# TS-ARM3_0_9.net
KiCad netlist of a schematic drawn in EAGLE
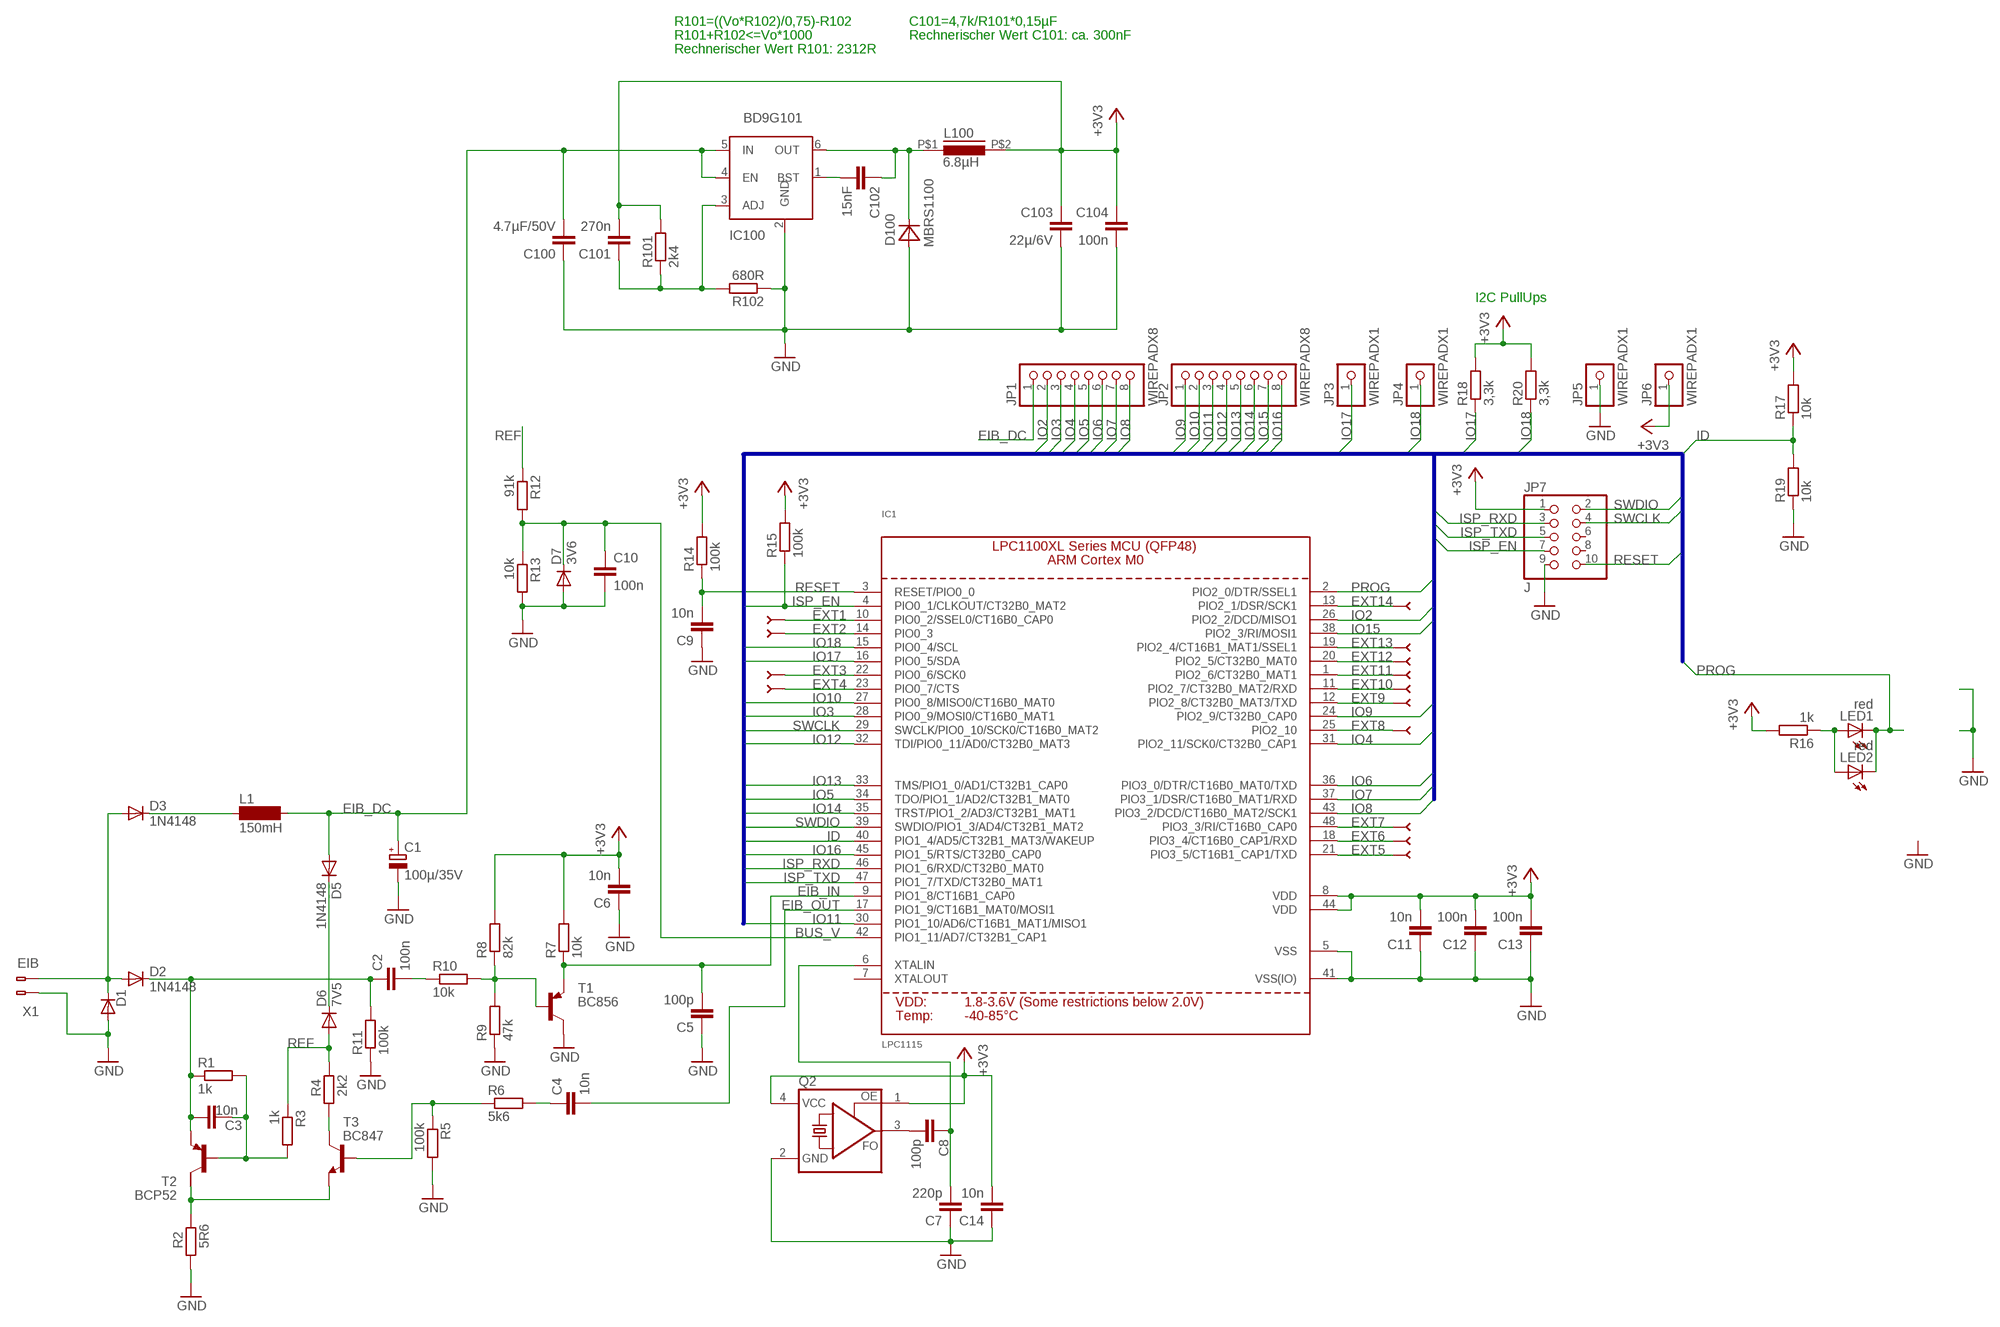
[diagram p0: schematic, sheet 1]

(export (version "E")
  (design (tool "Eeschema 10.0.6"))
  (components
    (comp (ref "C1")
      (value "100µ/35V")
      (footprint "eagle-import:SANYO-OSCON_SMD_C6")
      (libsource (lib "eagle-import") (part "CPOL-EUSANYO_SMD_C6"))
    )
    (comp (ref "C2")
      (value "100n")
      (footprint "eagle-import:C1206")
      (libsource (lib "eagle-import") (part "C-EUC1206"))
    )
    (comp (ref "C3")
      (value "10n")
      (footprint "eagle-import:C1206")
      (libsource (lib "eagle-import") (part "C-EUC1206"))
    )
    (comp (ref "C4")
      (value "10n")
      (footprint "eagle-import:C1206")
      (libsource (lib "eagle-import") (part "C-EUC1206"))
    )
    (comp (ref "C5")
      (value "100p")
      (footprint "eagle-import:C1206")
      (libsource (lib "eagle-import") (part "C-EUC1206"))
    )
    (comp (ref "C6")
      (value "10n")
      (footprint "eagle-import:C1206")
      (libsource (lib "eagle-import") (part "C-EUC1206"))
    )
    (comp (ref "C7")
      (value "220p")
      (footprint "eagle-import:C1206")
      (libsource (lib "eagle-import") (part "C-EUC1206"))
    )
    (comp (ref "C8")
      (value "100p")
      (footprint "eagle-import:C1206")
      (libsource (lib "eagle-import") (part "C-EUC1206"))
    )
    (comp (ref "C9")
      (value "10n")
      (footprint "eagle-import:C1206")
      (libsource (lib "eagle-import") (part "C-EUC1206"))
    )
    (comp (ref "C10")
      (value "100n")
      (footprint "eagle-import:C1206")
      (libsource (lib "eagle-import") (part "C-EUC1206"))
    )
    (comp (ref "C11")
      (value "10n")
      (footprint "eagle-import:C1206")
      (libsource (lib "eagle-import") (part "C-EUC1206"))
    )
    (comp (ref "C12")
      (value "100n")
      (footprint "eagle-import:C1206")
      (libsource (lib "eagle-import") (part "C-EUC1206"))
    )
    (comp (ref "C13")
      (value "100n")
      (footprint "eagle-import:C1206")
      (libsource (lib "eagle-import") (part "C-EUC1206"))
    )
    (comp (ref "C14")
      (value "10n")
      (footprint "eagle-import:C1206")
      (libsource (lib "eagle-import") (part "C-EUC1206"))
    )
    (comp (ref "C100")
      (value "4.7µF/50V")
      (footprint "eagle-import:C1206")
      (libsource (lib "eagle-import") (part "C-EUC1206"))
    )
    (comp (ref "C101")
      (value "270n")
      (footprint "eagle-import:C1206")
      (libsource (lib "eagle-import") (part "C-EUC1206"))
    )
    (comp (ref "C102")
      (value "15nF")
      (footprint "eagle-import:C1206")
      (libsource (lib "eagle-import") (part "C-EUC1206"))
    )
    (comp (ref "C103")
      (value "22µ/6V")
      (footprint "eagle-import:C1206")
      (libsource (lib "eagle-import") (part "C-EUC1206"))
    )
    (comp (ref "C104")
      (value "100n")
      (footprint "eagle-import:C1206")
      (libsource (lib "eagle-import") (part "C-EUC1206"))
    )
    (comp (ref "D1")
      (value "SMAJ40C")
      (footprint "eagle-import:SMB")
      (libsource (lib "eagle-import") (part "D-SMB"))
    )
    (comp (ref "D2")
      (value "1N4148")
      (footprint "eagle-import:MINIMELF")
      (libsource (lib "eagle-import") (part "DIODE-MINIMELF"))
    )
    (comp (ref "D3")
      (value "1N4148")
      (footprint "eagle-import:MINIMELF")
      (libsource (lib "eagle-import") (part "DIODE-MINIMELF"))
    )
    (comp (ref "D5")
      (value "1N4148")
      (footprint "eagle-import:MINIMELF")
      (libsource (lib "eagle-import") (part "DIODE-MINIMELF"))
    )
    (comp (ref "D6")
      (value "7V5")
      (footprint "eagle-import:MINIMELF")
      (libsource (lib "eagle-import") (part "DIODE-MINIMELF"))
    )
    (comp (ref "D7")
      (value "3V6")
      (footprint "eagle-import:MINIMELF")
      (libsource (lib "eagle-import") (part "DIODE-MINIMELF"))
    )
    (comp (ref "D100")
      (value "MBRS1100")
      (footprint "eagle-import:SMA")
      (libsource (lib "eagle-import") (part "MBRA340T3"))
    )
    (comp (ref "IC1")
      (value "LPC1115")
      (footprint "eagle-import:LQFP48")
      (libsource (lib "eagle-import") (part "LPC1113/4/5_QFP48_XLSERIES"))
    )
    (comp (ref "IC100")
      (value "BD9G101")
      (footprint "eagle-import:SOT23-6")
      (libsource (lib "eagle-import") (part "BD9G101GBD9G101G-SOT23-6"))
    )
    (comp (ref "JP1")
      (value "WIREPADX8")
      (footprint "eagle-import:SMD1,27X2,54X8")
      (libsource (lib "eagle-import") (part "WIREPADX8"))
    )
    (comp (ref "JP2")
      (value "WIREPADX8")
      (footprint "eagle-import:SMD1,27X2,54X8")
      (libsource (lib "eagle-import") (part "WIREPADX8"))
    )
    (comp (ref "JP3")
      (value "WIREPADX1")
      (footprint "eagle-import:SMD1,27X2,54")
      (libsource (lib "eagle-import") (part "WIREPADX1"))
    )
    (comp (ref "JP4")
      (value "WIREPADX1")
      (footprint "eagle-import:SMD1,27X2,54")
      (libsource (lib "eagle-import") (part "WIREPADX1"))
    )
    (comp (ref "JP5")
      (value "WIREPADX1")
      (footprint "eagle-import:SMD1,27X2,54")
      (libsource (lib "eagle-import") (part "WIREPADX1"))
    )
    (comp (ref "JP6")
      (value "WIREPADX1")
      (footprint "eagle-import:SMD1,27X2,54")
      (libsource (lib "eagle-import") (part "WIREPADX1"))
    )
    (comp (ref "JP7")
      (value "J")
      (footprint "eagle-import:2X05M")
      (libsource (lib "eagle-import") (part "PINHD-2X05_2.00"))
    )
    (comp (ref "L1")
      (value "150mH")
      (footprint "eagle-import:SD12_1000")
      (libsource (lib "eagle-import") (part "SD12-1000"))
    )
    (comp (ref "L100")
      (value "6.8µH")
      (footprint "eagle-import:PIS2812")
      (libsource (lib "eagle-import") (part "IND_FASTRON_1616FPS"))
    )
    (comp (ref "LED1")
      (value "red")
      (footprint "eagle-import:CHIPLED_1206")
      (libsource (lib "eagle-import") (part "LEDCHIPLED_1206"))
    )
    (comp (ref "LED2")
      (value "red")
      (footprint "eagle-import:LED3MM")
      (libsource (lib "eagle-import") (part "LED3MM"))
    )
    (comp (ref "P1")
      (value "PAD")
      (footprint "eagle-import:PAD")
      (libsource (lib "eagle-import") (part "PAD"))
    )
    (comp (ref "P2")
      (value "PAD")
      (footprint "eagle-import:PAD")
      (libsource (lib "eagle-import") (part "PAD"))
    )
    (comp (ref "P3")
      (value "PAD")
      (footprint "eagle-import:PAD")
      (libsource (lib "eagle-import") (part "PAD"))
    )
    (comp (ref "P4")
      (value "PAD")
      (footprint "eagle-import:PAD")
      (libsource (lib "eagle-import") (part "PAD"))
    )
    (comp (ref "P5")
      (value "PAD")
      (footprint "eagle-import:PAD")
      (libsource (lib "eagle-import") (part "PAD"))
    )
    (comp (ref "P6")
      (value "PAD")
      (footprint "eagle-import:PAD")
      (libsource (lib "eagle-import") (part "PAD"))
    )
    (comp (ref "P7")
      (value "PAD")
      (footprint "eagle-import:PAD")
      (libsource (lib "eagle-import") (part "PAD"))
    )
    (comp (ref "P8")
      (value "PAD")
      (footprint "eagle-import:PAD")
      (libsource (lib "eagle-import") (part "PAD"))
    )
    (comp (ref "P9")
      (value "PAD")
      (footprint "eagle-import:PAD")
      (libsource (lib "eagle-import") (part "PAD"))
    )
    (comp (ref "P10")
      (value "PAD")
      (footprint "eagle-import:PAD")
      (libsource (lib "eagle-import") (part "PAD"))
    )
    (comp (ref "P11")
      (value "PAD")
      (footprint "eagle-import:PAD")
      (libsource (lib "eagle-import") (part "PAD"))
    )
    (comp (ref "P12")
      (value "PAD")
      (footprint "eagle-import:PAD")
      (libsource (lib "eagle-import") (part "PAD"))
    )
    (comp (ref "P13")
      (value "PAD")
      (footprint "eagle-import:PAD")
      (libsource (lib "eagle-import") (part "PAD"))
    )
    (comp (ref "P14")
      (value "PAD")
      (footprint "eagle-import:PAD")
      (libsource (lib "eagle-import") (part "PAD"))
    )
    (comp (ref "Q2")
      (value "ASFL")
      (footprint "eagle-import:ASF")
      (libsource (lib "eagle-import") (part "ASFL"))
    )
    (comp (ref "R1")
      (value "1k")
      (footprint "eagle-import:R1206")
      (libsource (lib "eagle-import") (part "R-EU_R1206"))
    )
    (comp (ref "R2")
      (value "5R6")
      (footprint "eagle-import:R1206")
      (libsource (lib "eagle-import") (part "R-EU_R1206"))
    )
    (comp (ref "R3")
      (value "1k")
      (footprint "eagle-import:R1206")
      (libsource (lib "eagle-import") (part "R-EU_R1206"))
    )
    (comp (ref "R4")
      (value "2k2")
      (footprint "eagle-import:R1206")
      (libsource (lib "eagle-import") (part "R-EU_R1206"))
    )
    (comp (ref "R5")
      (value "100k")
      (footprint "eagle-import:R1206")
      (libsource (lib "eagle-import") (part "R-EU_R1206"))
    )
    (comp (ref "R6")
      (value "5k6")
      (footprint "eagle-import:R1206")
      (libsource (lib "eagle-import") (part "R-EU_R1206"))
    )
    (comp (ref "R7")
      (value "10k")
      (footprint "eagle-import:R1206")
      (libsource (lib "eagle-import") (part "R-EU_R1206"))
    )
    (comp (ref "R8")
      (value "82k")
      (footprint "eagle-import:R1206")
      (libsource (lib "eagle-import") (part "R-EU_R1206"))
    )
    (comp (ref "R9")
      (value "47k")
      (footprint "eagle-import:R1206")
      (libsource (lib "eagle-import") (part "R-EU_R1206"))
    )
    (comp (ref "R10")
      (value "10k")
      (footprint "eagle-import:R1206")
      (libsource (lib "eagle-import") (part "R-EU_R1206"))
    )
    (comp (ref "R11")
      (value "100k")
      (footprint "eagle-import:R1206")
      (libsource (lib "eagle-import") (part "R-EU_R1206"))
    )
    (comp (ref "R12")
      (value "91k")
      (footprint "eagle-import:R1206")
      (libsource (lib "eagle-import") (part "R-EU_R1206"))
    )
    (comp (ref "R13")
      (value "10k")
      (footprint "eagle-import:R1206")
      (libsource (lib "eagle-import") (part "R-EU_R1206"))
    )
    (comp (ref "R14")
      (value "100k")
      (footprint "eagle-import:R1206")
      (libsource (lib "eagle-import") (part "R-EU_R1206"))
    )
    (comp (ref "R15")
      (value "100k")
      (footprint "eagle-import:R1206")
      (libsource (lib "eagle-import") (part "R-EU_R1206"))
    )
    (comp (ref "R16")
      (value "1k")
      (footprint "eagle-import:R1206")
      (libsource (lib "eagle-import") (part "R-EU_R1206"))
    )
    (comp (ref "R17")
      (value "10k")
      (footprint "eagle-import:R1206")
      (libsource (lib "eagle-import") (part "R-EU_R1206"))
    )
    (comp (ref "R18")
      (value "3,3k")
      (footprint "eagle-import:R1206")
      (libsource (lib "eagle-import") (part "R-EU_R1206"))
    )
    (comp (ref "R19")
      (value "10k")
      (footprint "eagle-import:R1206")
      (libsource (lib "eagle-import") (part "R-EU_R1206"))
    )
    (comp (ref "R20")
      (value "3,3k")
      (footprint "eagle-import:R1206")
      (libsource (lib "eagle-import") (part "R-EU_R1206"))
    )
    (comp (ref "R101")
      (value "2k4")
      (footprint "eagle-import:R1206")
      (libsource (lib "eagle-import") (part "R-EU_R1206"))
    )
    (comp (ref "R102")
      (value "680R")
      (footprint "eagle-import:R1206")
      (libsource (lib "eagle-import") (part "R-EU_R1206"))
    )
    (comp (ref "T1")
      (value "BC856")
      (footprint "eagle-import:SOT23-BEC")
      (libsource (lib "eagle-import") (part "BC856SMDB"))
    )
    (comp (ref "T2")
      (value "BCP52")
      (footprint "eagle-import:SOT223")
      (libsource (lib "eagle-import") (part "FZT753SMD"))
    )
    (comp (ref "T3")
      (value "BC847")
      (footprint "eagle-import:SOT23")
      (libsource (lib "eagle-import") (part "BC847"))
    )
    (comp (ref "X1")
      (value "EIB")
      (footprint "eagle-import:BUSKLEMME243-724")
      (libsource (lib "eagle-import") (part "EIB"))
    )
  )
  (nets
    (net (code "1") (name "+3V3") (class "Default")
      (node (ref "C101") (pin "2") (pinfunction "2_2") (pintype "passive"))
      (node (ref "C103") (pin "1") (pinfunction "1_1") (pintype "passive"))
      (node (ref "C104") (pin "1") (pinfunction "1_1") (pintype "passive"))
      (node (ref "C11") (pin "2") (pinfunction "2_2") (pintype "passive"))
      (node (ref "C12") (pin "2") (pinfunction "2_2") (pintype "passive"))
      (node (ref "C13") (pin "2") (pinfunction "2_2") (pintype "passive"))
      (node (ref "C14") (pin "2") (pinfunction "2_2") (pintype "passive"))
      (node (ref "C6") (pin "2") (pinfunction "2_2") (pintype "passive"))
      (node (ref "IC1") (pin "44") (pinfunction "VDD_44") (pintype "power_in"))
      (node (ref "IC1") (pin "8") (pinfunction "VDD_8") (pintype "power_in"))
      (node (ref "JP6") (pin "1") (pinfunction "1_1") (pintype "passive"))
      (node (ref "JP7") (pin "1") (pinfunction "1_1") (pintype "passive"))
      (node (ref "L100") (pin "P$2") (pinfunction "2_P$2") (pintype "passive"))
      (node (ref "Q2") (pin "1") (pinfunction "OE_1") (pintype "input"))
      (node (ref "Q2") (pin "4") (pinfunction "VCC_4") (pintype "power_in"))
      (node (ref "R101") (pin "2") (pinfunction "2_2") (pintype "passive"))
      (node (ref "R14") (pin "2") (pinfunction "2_2") (pintype "passive"))
      (node (ref "R15") (pin "2") (pinfunction "2_2") (pintype "passive"))
      (node (ref "R16") (pin "2") (pinfunction "2_2") (pintype "passive"))
      (node (ref "R17") (pin "2") (pinfunction "2_2") (pintype "passive"))
      (node (ref "R18") (pin "2") (pinfunction "2_2") (pintype "passive"))
      (node (ref "R20") (pin "2") (pinfunction "2_2") (pintype "passive"))
      (node (ref "R7") (pin "2") (pinfunction "2_2") (pintype "passive"))
      (node (ref "R8") (pin "2") (pinfunction "2_2") (pintype "passive"))
    )
    (net (code "2") (name "/BUS_V") (class "Default")
      (node (ref "C10") (pin "2") (pinfunction "2_2") (pintype "passive"))
      (node (ref "D7") (pin "C") (pinfunction "C_C") (pintype "passive"))
      (node (ref "IC1") (pin "42") (pinfunction "PIO1_11/AD7/CT32B1_CAP1_42") (pintype "bidirectional"))
      (node (ref "R12") (pin "2") (pinfunction "2_2") (pintype "passive"))
      (node (ref "R13") (pin "1") (pinfunction "1_1") (pintype "passive"))
    )
    (net (code "3") (name "/EIB_DC") (class "Default")
      (node (ref "C1") (pin "+") (pinfunction "+_+") (pintype "passive"))
      (node (ref "C100") (pin "2") (pinfunction "2_2") (pintype "passive"))
      (node (ref "D5") (pin "A") (pinfunction "A_A") (pintype "passive"))
      (node (ref "IC100") (pin "4") (pinfunction "EN_4") (pintype "input"))
      (node (ref "IC100") (pin "5") (pinfunction "IN_5") (pintype "input"))
      (node (ref "JP1") (pin "1") (pinfunction "1_1") (pintype "passive"))
      (node (ref "L1") (pin "2") (pinfunction "2_2") (pintype "passive"))
    )
    (net (code "4") (name "/EIB_IN") (class "Default")
      (node (ref "C5") (pin "2") (pinfunction "2_2") (pintype "passive"))
      (node (ref "IC1") (pin "9") (pinfunction "PIO1_8/CT16B1_CAP0_9") (pintype "bidirectional"))
      (node (ref "R7") (pin "1") (pinfunction "1_1") (pintype "passive"))
      (node (ref "T1") (pin "E") (pinfunction "E_E") (pintype "passive"))
    )
    (net (code "5") (name "/EIB_OUT") (class "Default")
      (node (ref "C4") (pin "2") (pinfunction "2_2") (pintype "passive"))
      (node (ref "IC1") (pin "17") (pinfunction "PIO1_9/CT16B1_MAT0/MOSI1_17") (pintype "bidirectional"))
    )
    (net (code "6") (name "/EXT1") (class "Default")
      (node (ref "IC1") (pin "10") (pinfunction "PIO0_2/SSEL0/CT16B0_CAP0_10") (pintype "bidirectional"))
      (node (ref "P1") (pin "1") (pinfunction "1_1") (pintype "bidirectional"))
    )
    (net (code "7") (name "/EXT2") (class "Default")
      (node (ref "IC1") (pin "14") (pinfunction "PIO0_3_14") (pintype "bidirectional"))
      (node (ref "P2") (pin "1") (pinfunction "1_1") (pintype "bidirectional"))
    )
    (net (code "8") (name "/EXT3") (class "Default")
      (node (ref "IC1") (pin "22") (pinfunction "PIO0_6/SCK0_22") (pintype "bidirectional"))
      (node (ref "P13") (pin "1") (pinfunction "1_1") (pintype "bidirectional"))
    )
    (net (code "9") (name "/EXT4") (class "Default")
      (node (ref "IC1") (pin "23") (pinfunction "PIO0_7/CTS_23") (pintype "bidirectional"))
      (node (ref "P14") (pin "1") (pinfunction "1_1") (pintype "bidirectional"))
    )
    (net (code "10") (name "/EXT5") (class "Default")
      (node (ref "IC1") (pin "21") (pinfunction "PIO3_5/CT16B1_CAP1/TXD_21") (pintype "bidirectional"))
      (node (ref "P12") (pin "1") (pinfunction "1_1") (pintype "bidirectional"))
    )
    (net (code "11") (name "/EXT6") (class "Default")
      (node (ref "IC1") (pin "18") (pinfunction "PIO3_4/CT16B0_CAP1/RXD_18") (pintype "bidirectional"))
      (node (ref "P11") (pin "1") (pinfunction "1_1") (pintype "bidirectional"))
    )
    (net (code "12") (name "/EXT7") (class "Default")
      (node (ref "IC1") (pin "48") (pinfunction "PIO3_3/RI/CT16B0_CAP0_48") (pintype "bidirectional"))
      (node (ref "P10") (pin "1") (pinfunction "1_1") (pintype "bidirectional"))
    )
    (net (code "13") (name "/EXT8") (class "Default")
      (node (ref "IC1") (pin "25") (pinfunction "PIO2_10_25") (pintype "bidirectional"))
      (node (ref "P6") (pin "1") (pinfunction "1_1") (pintype "bidirectional"))
    )
    (net (code "14") (name "/EXT9") (class "Default")
      (node (ref "IC1") (pin "12") (pinfunction "PIO2_8/CT32B0_MAT3/TXD_12") (pintype "bidirectional"))
      (node (ref "P4") (pin "1") (pinfunction "1_1") (pintype "bidirectional"))
    )
    (net (code "15") (name "/EXT10") (class "Default")
      (node (ref "IC1") (pin "11") (pinfunction "PIO2_7/CT32B0_MAT2/RXD_11") (pintype "bidirectional"))
      (node (ref "P5") (pin "1") (pinfunction "1_1") (pintype "bidirectional"))
    )
    (net (code "16") (name "/EXT11") (class "Default")
      (node (ref "IC1") (pin "1") (pinfunction "PIO2_6/CT32B0_MAT1_1") (pintype "bidirectional"))
      (node (ref "P9") (pin "1") (pinfunction "1_1") (pintype "bidirectional"))
    )
    (net (code "17") (name "/EXT12") (class "Default")
      (node (ref "IC1") (pin "20") (pinfunction "PIO2_5/CT32B0_MAT0_20") (pintype "bidirectional"))
      (node (ref "P8") (pin "1") (pinfunction "1_1") (pintype "bidirectional"))
    )
    (net (code "18") (name "/EXT13") (class "Default")
      (node (ref "IC1") (pin "19") (pinfunction "PIO2_4/CT16B1_MAT1/SSEL1_19") (pintype "bidirectional"))
      (node (ref "P7") (pin "1") (pinfunction "1_1") (pintype "bidirectional"))
    )
    (net (code "19") (name "/EXT14") (class "Default")
      (node (ref "IC1") (pin "13") (pinfunction "PIO2_1/DSR/SCK1_13") (pintype "bidirectional"))
      (node (ref "P3") (pin "1") (pinfunction "1_1") (pintype "bidirectional"))
    )
    (net (code "20") (name "/ID") (class "Default")
      (node (ref "IC1") (pin "40") (pinfunction "PIO1_4/AD5/CT32B1_MAT3/WAKEUP_40") (pintype "bidirectional"))
      (node (ref "R17") (pin "1") (pinfunction "1_1") (pintype "passive"))
      (node (ref "R19") (pin "2") (pinfunction "2_2") (pintype "passive"))
    )
    (net (code "21") (name "/IO2") (class "Default")
      (node (ref "IC1") (pin "26") (pinfunction "PIO2_2/DCD/MISO1_26") (pintype "bidirectional"))
      (node (ref "JP1") (pin "2") (pinfunction "2_2") (pintype "passive"))
    )
    (net (code "22") (name "/IO3") (class "Default")
      (node (ref "IC1") (pin "28") (pinfunction "PIO0_9/MOSI0/CT16B0_MAT1_28") (pintype "bidirectional"))
      (node (ref "JP1") (pin "3") (pinfunction "3_3") (pintype "passive"))
    )
    (net (code "23") (name "/IO4") (class "Default")
      (node (ref "IC1") (pin "31") (pinfunction "PIO2_11/SCK0/CT32B0_CAP1_31") (pintype "bidirectional"))
      (node (ref "JP1") (pin "4") (pinfunction "4_4") (pintype "passive"))
    )
    (net (code "24") (name "/IO5") (class "Default")
      (node (ref "IC1") (pin "34") (pinfunction "TDO/PIO1_1/AD2/CT32B1_MAT0_34") (pintype "bidirectional"))
      (node (ref "JP1") (pin "5") (pinfunction "5_5") (pintype "passive"))
    )
    (net (code "25") (name "/IO6") (class "Default")
      (node (ref "IC1") (pin "36") (pinfunction "PIO3_0/DTR/CT16B0_MAT0/TXD_36") (pintype "bidirectional"))
      (node (ref "JP1") (pin "6") (pinfunction "6_6") (pintype "passive"))
    )
    (net (code "26") (name "/IO7") (class "Default")
      (node (ref "IC1") (pin "37") (pinfunction "PIO3_1/DSR/CT16B0_MAT1/RXD_37") (pintype "bidirectional"))
      (node (ref "JP1") (pin "7") (pinfunction "7_7") (pintype "passive"))
    )
    (net (code "27") (name "/IO8") (class "Default")
      (node (ref "IC1") (pin "43") (pinfunction "PIO3_2/DCD/CT16B0_MAT2/SCK1_43") (pintype "bidirectional"))
      (node (ref "JP1") (pin "8") (pinfunction "8_8") (pintype "passive"))
    )
    (net (code "28") (name "/IO9") (class "Default")
      (node (ref "IC1") (pin "24") (pinfunction "PIO2_9/CT32B0_CAP0_24") (pintype "bidirectional"))
      (node (ref "JP2") (pin "1") (pinfunction "1_1") (pintype "passive"))
    )
    (net (code "29") (name "/IO10") (class "Default")
      (node (ref "IC1") (pin "27") (pinfunction "PIO0_8/MISO0/CT16B0_MAT0_27") (pintype "bidirectional"))
      (node (ref "JP2") (pin "2") (pinfunction "2_2") (pintype "passive"))
    )
    (net (code "30") (name "/IO11") (class "Default")
      (node (ref "IC1") (pin "30") (pinfunction "PIO1_10/AD6/CT16B1_MAT1/MISO1_30") (pintype "bidirectional"))
      (node (ref "JP2") (pin "3") (pinfunction "3_3") (pintype "passive"))
    )
    (net (code "31") (name "/IO12") (class "Default")
      (node (ref "IC1") (pin "32") (pinfunction "TDI/PIO0_11/AD0/CT32B0_MAT3_32") (pintype "bidirectional"))
      (node (ref "JP2") (pin "4") (pinfunction "4_4") (pintype "passive"))
    )
    (net (code "32") (name "/IO13") (class "Default")
      (node (ref "IC1") (pin "33") (pinfunction "TMS/PIO1_0/AD1/CT32B1_CAP0_33") (pintype "bidirectional"))
      (node (ref "JP2") (pin "5") (pinfunction "5_5") (pintype "passive"))
    )
    (net (code "33") (name "/IO14") (class "Default")
      (node (ref "IC1") (pin "35") (pinfunction "TRST/PIO1_2/AD3/CT32B1_MAT1_35") (pintype "bidirectional"))
      (node (ref "JP2") (pin "6") (pinfunction "6_6") (pintype "passive"))
    )
    (net (code "34") (name "/IO15") (class "Default")
      (node (ref "IC1") (pin "38") (pinfunction "PIO2_3/RI/MOSI1_38") (pintype "bidirectional"))
      (node (ref "JP2") (pin "7") (pinfunction "7_7") (pintype "passive"))
    )
    (net (code "35") (name "/IO16") (class "Default")
      (node (ref "IC1") (pin "45") (pinfunction "PIO1_5/RTS/CT32B0_CAP0_45") (pintype "bidirectional"))
      (node (ref "JP2") (pin "8") (pinfunction "8_8") (pintype "passive"))
    )
    (net (code "36") (name "/IO17") (class "Default")
      (node (ref "IC1") (pin "16") (pinfunction "PIO0_5/SDA_16") (pintype "bidirectional"))
      (node (ref "JP3") (pin "1") (pinfunction "1_1") (pintype "passive"))
      (node (ref "R18") (pin "1") (pinfunction "1_1") (pintype "passive"))
    )
    (net (code "37") (name "/IO18") (class "Default")
      (node (ref "IC1") (pin "15") (pinfunction "PIO0_4/SCL_15") (pintype "bidirectional"))
      (node (ref "JP4") (pin "1") (pinfunction "1_1") (pintype "passive"))
      (node (ref "R20") (pin "1") (pinfunction "1_1") (pintype "passive"))
    )
    (net (code "38") (name "/ISP_EN") (class "Default")
      (node (ref "IC1") (pin "4") (pinfunction "PIO0_1/CLKOUT/CT32B0_MAT2_4") (pintype "bidirectional"))
      (node (ref "JP7") (pin "7") (pinfunction "7_7") (pintype "passive"))
      (node (ref "R15") (pin "1") (pinfunction "1_1") (pintype "passive"))
    )
    (net (code "39") (name "/ISP_RXD") (class "Default")
      (node (ref "IC1") (pin "46") (pinfunction "PIO1_6/RXD/CT32B0_MAT0_46") (pintype "bidirectional"))
      (node (ref "JP7") (pin "3") (pinfunction "3_3") (pintype "passive"))
    )
    (net (code "40") (name "/ISP_TXD") (class "Default")
      (node (ref "IC1") (pin "47") (pinfunction "PIO1_7/TXD/CT32B0_MAT1_47") (pintype "bidirectional"))
      (node (ref "JP7") (pin "5") (pinfunction "5_5") (pintype "passive"))
    )
    (net (code "41") (name "/PROG") (class "Default")
      (node (ref "IC1") (pin "2") (pinfunction "PIO2_0/DTR/SSEL1_2") (pintype "bidirectional"))
      (node (ref "LED1") (pin "C") (pinfunction "C_C") (pintype "passive"))
      (node (ref "LED2") (pin "K") (pinfunction "C_K") (pintype "passive"))
    )
    (net (code "42") (name "/REF") (class "Default")
      (node (ref "D6") (pin "A") (pinfunction "A_A") (pintype "passive"))
      (node (ref "R12") (pin "1") (pinfunction "1_1") (pintype "passive"))
      (node (ref "R3") (pin "1") (pinfunction "1_1") (pintype "passive"))
      (node (ref "R4") (pin "2") (pinfunction "2_2") (pintype "passive"))
    )
    (net (code "43") (name "/RESET") (class "Default")
      (node (ref "C9") (pin "2") (pinfunction "2_2") (pintype "passive"))
      (node (ref "IC1") (pin "3") (pinfunction "RESET/PIO0_0_3") (pintype "bidirectional"))
      (node (ref "JP7") (pin "10") (pinfunction "10_10") (pintype "passive"))
      (node (ref "R14") (pin "1") (pinfunction "1_1") (pintype "passive"))
    )
    (net (code "44") (name "/SWCLK") (class "Default")
      (node (ref "IC1") (pin "29") (pinfunction "SWCLK/PIO0_10/SCK0/CT16B0_MAT2_29") (pintype "bidirectional"))
      (node (ref "JP7") (pin "4") (pinfunction "4_4") (pintype "passive"))
    )
    (net (code "45") (name "/SWDIO") (class "Default")
      (node (ref "IC1") (pin "39") (pinfunction "SWDIO/PIO1_3/AD4/CT32B1_MAT2_39") (pintype "bidirectional"))
      (node (ref "JP7") (pin "2") (pinfunction "2_2") (pintype "passive"))
    )
    (net (code "46") (name "GND") (class "Default")
      (node (ref "C1") (pin "-") (pinfunction "-_-") (pintype "passive"))
      (node (ref "C10") (pin "1") (pinfunction "1_1") (pintype "passive"))
      (node (ref "C100") (pin "1") (pinfunction "1_1") (pintype "passive"))
      (node (ref "C103") (pin "2") (pinfunction "2_2") (pintype "passive"))
      (node (ref "C104") (pin "2") (pinfunction "2_2") (pintype "passive"))
      (node (ref "C11") (pin "1") (pinfunction "1_1") (pintype "passive"))
      (node (ref "C12") (pin "1") (pinfunction "1_1") (pintype "passive"))
      (node (ref "C13") (pin "1") (pinfunction "1_1") (pintype "passive"))
      (node (ref "C14") (pin "1") (pinfunction "1_1") (pintype "passive"))
      (node (ref "C5") (pin "1") (pinfunction "1_1") (pintype "passive"))
      (node (ref "C6") (pin "1") (pinfunction "1_1") (pintype "passive"))
      (node (ref "C7") (pin "1") (pinfunction "1_1") (pintype "passive"))
      (node (ref "C9") (pin "1") (pinfunction "1_1") (pintype "passive"))
      (node (ref "D1") (pin "2") (pinfunction "A_2") (pintype "passive"))
      (node (ref "D100") (pin "A") (pinfunction "A_A") (pintype "passive"))
      (node (ref "D7") (pin "A") (pinfunction "A_A") (pintype "passive"))
      (node (ref "IC1") (pin "41") (pinfunction "VSS(IO)_41") (pintype "power_in"))
      (node (ref "IC1") (pin "5") (pinfunction "VSS_5") (pintype "power_in"))
      (node (ref "IC100") (pin "2") (pinfunction "GND_2") (pintype "power_in"))
      (node (ref "JP5") (pin "1") (pinfunction "1_1") (pintype "passive"))
      (node (ref "JP7") (pin "9") (pinfunction "9_9") (pintype "passive"))
      (node (ref "Q2") (pin "2") (pinfunction "GND_2") (pintype "power_in"))
      (node (ref "R102") (pin "1") (pinfunction "1_1") (pintype "passive"))
      (node (ref "R11") (pin "1") (pinfunction "1_1") (pintype "passive"))
      (node (ref "R13") (pin "2") (pinfunction "2_2") (pintype "passive"))
      (node (ref "R19") (pin "1") (pinfunction "1_1") (pintype "passive"))
      (node (ref "R2") (pin "1") (pinfunction "1_1") (pintype "passive"))
      (node (ref "R5") (pin "2") (pinfunction "2_2") (pintype "passive"))
      (node (ref "R9") (pin "1") (pinfunction "1_1") (pintype "passive"))
      (node (ref "T1") (pin "C") (pinfunction "C_C") (pintype "passive"))
      (node (ref "X1") (pin "1") (pinfunction "B-1_1") (pintype "passive"))
    )
    (net (code "47") (name "Net-(C2-Pad2)") (class "Default")
      (node (ref "C2") (pin "2") (pinfunction "2_2") (pintype "passive"))
      (node (ref "R10") (pin "1") (pinfunction "1_1") (pintype "passive"))
    )
    (net (code "48") (name "Net-(C4-Pad1)") (class "Default")
      (node (ref "C4") (pin "1") (pinfunction "1_1") (pintype "passive"))
      (node (ref "R6") (pin "2") (pinfunction "2_2") (pintype "passive"))
    )
    (net (code "49") (name "Net-(D1-C)") (class "Default")
      (node (ref "D1") (pin "1") (pinfunction "C_1") (pintype "passive"))
      (node (ref "D2") (pin "A") (pinfunction "A_A") (pintype "passive"))
      (node (ref "D3") (pin "A") (pinfunction "A_A") (pintype "passive"))
      (node (ref "X1") (pin "2") (pinfunction "B-2_2") (pintype "passive"))
    )
    (net (code "50") (name "Net-(D3-PadC)") (class "Default")
      (node (ref "D3") (pin "C") (pinfunction "C_C") (pintype "passive"))
      (node (ref "L1") (pin "1") (pinfunction "1_1") (pintype "passive"))
    )
    (net (code "51") (name "Net-(D5-PadC)") (class "Default")
      (node (ref "D5") (pin "C") (pinfunction "C_C") (pintype "passive"))
      (node (ref "D6") (pin "C") (pinfunction "C_C") (pintype "passive"))
    )
    (net (code "52") (name "Net-(IC1-XTALIN)") (class "Default")
      (node (ref "C7") (pin "2") (pinfunction "2_2") (pintype "passive"))
      (node (ref "C8") (pin "1") (pinfunction "1_1") (pintype "passive"))
      (node (ref "IC1") (pin "6") (pinfunction "XTALIN_6") (pintype "input"))
    )
    (net (code "53") (name "Net-(IC100-ADJ)") (class "Default")
      (node (ref "C101") (pin "1") (pinfunction "1_1") (pintype "passive"))
      (node (ref "IC100") (pin "3") (pinfunction "ADJ_3") (pintype "passive"))
      (node (ref "R101") (pin "1") (pinfunction "1_1") (pintype "passive"))
      (node (ref "R102") (pin "2") (pinfunction "2_2") (pintype "passive"))
    )
    (net (code "54") (name "Net-(IC100-BST)") (class "Default")
      (node (ref "C102") (pin "2") (pinfunction "2_2") (pintype "passive"))
      (node (ref "IC100") (pin "1") (pinfunction "BST_1") (pintype "output"))
    )
    (net (code "55") (name "Net-(IC100-OUT)") (class "Default")
      (node (ref "C102") (pin "1") (pinfunction "1_1") (pintype "passive"))
      (node (ref "D100") (pin "C") (pinfunction "C_C") (pintype "passive"))
      (node (ref "IC100") (pin "6") (pinfunction "OUT_6") (pintype "output"))
      (node (ref "L100") (pin "P$1") (pinfunction "1_P$1") (pintype "passive"))
    )
    (net (code "56") (name "Net-(LED1-PadA)") (class "Default")
      (node (ref "LED1") (pin "A") (pinfunction "A_A") (pintype "passive"))
      (node (ref "LED2") (pin "A") (pinfunction "A_A") (pintype "passive"))
      (node (ref "R16") (pin "1") (pinfunction "1_1") (pintype "passive"))
    )
    (net (code "57") (name "Net-(Q2-FO)") (class "Default")
      (node (ref "C8") (pin "2") (pinfunction "2_2") (pintype "passive"))
      (node (ref "Q2") (pin "3") (pinfunction "FO_3") (pintype "output"))
    )
    (net (code "58") (name "Net-(R10-Pad2)") (class "Default")
      (node (ref "R10") (pin "2") (pinfunction "2_2") (pintype "passive"))
      (node (ref "R8") (pin "1") (pinfunction "1_1") (pintype "passive"))
      (node (ref "R9") (pin "2") (pinfunction "2_2") (pintype "passive"))
      (node (ref "T1") (pin "B") (pinfunction "B_B") (pintype "passive"))
    )
    (net (code "59") (name "Net-(T2-B)") (class "Default")
      (node (ref "C3") (pin "2") (pinfunction "2_2") (pintype "passive"))
      (node (ref "R1") (pin "2") (pinfunction "2_2") (pintype "passive"))
      (node (ref "R3") (pin "2") (pinfunction "2_2") (pintype "passive"))
      (node (ref "T2") (pin "1") (pinfunction "B_1") (pintype "passive"))
    )
    (net (code "60") (name "Net-(T2-C)") (class "Default")
      (node (ref "R2") (pin "2") (pinfunction "2_2") (pintype "passive"))
      (node (ref "T2") (pin "2") (pinfunction "C_2") (pintype "passive"))
      (node (ref "T3") (pin "2") (pinfunction "E_2") (pintype "passive"))
    )
    (net (code "61") (name "Net-(T2-E)") (class "Default")
      (node (ref "C2") (pin "1") (pinfunction "1_1") (pintype "passive"))
      (node (ref "C3") (pin "1") (pinfunction "1_1") (pintype "passive"))
      (node (ref "D2") (pin "C") (pinfunction "C_C") (pintype "passive"))
      (node (ref "R1") (pin "1") (pinfunction "1_1") (pintype "passive"))
      (node (ref "R11") (pin "2") (pinfunction "2_2") (pintype "passive"))
      (node (ref "T2") (pin "3") (pinfunction "E_3") (pintype "passive"))
    )
    (net (code "62") (name "Net-(T3-B)") (class "Default")
      (node (ref "R5") (pin "1") (pinfunction "1_1") (pintype "passive"))
      (node (ref "R6") (pin "1") (pinfunction "1_1") (pintype "passive"))
      (node (ref "T3") (pin "1") (pinfunction "B_1") (pintype "passive"))
    )
    (net (code "63") (name "Net-(T3-C)") (class "Default")
      (node (ref "R4") (pin "1") (pinfunction "1_1") (pintype "passive"))
      (node (ref "T3") (pin "3") (pinfunction "C_3") (pintype "passive"))
    )
    (net (code "64") (name "unconnected-(IC1-XTALOUT-Pad7)") (class "Default")
      (node (ref "IC1") (pin "7") (pinfunction "XTALOUT_7") (pintype "output"))
    )
    (net (code "65") (name "unconnected-(JP7-Pad6)") (class "Default")
      (node (ref "JP7") (pin "6") (pinfunction "6_6") (pintype "passive"))
    )
    (net (code "66") (name "unconnected-(JP7-Pad8)") (class "Default")
      (node (ref "JP7") (pin "8") (pinfunction "8_8") (pintype "passive"))
    )
    (net (code "67") (name "unconnected-(T2-C{slash}-Pad4)") (class "Default")
      (node (ref "T2") (pin "4") (pinfunction "C/_4") (pintype "passive"))
    )
  )
)
